# Linear_Regulator.net
KiCad netlist of a schematic drawn in Altium Designer
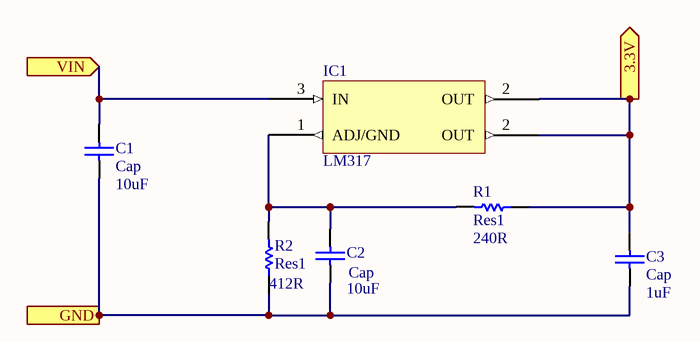
[diagram p0: Linear Regulator.SchDoc]

(export (version "E")
  (design (tool "Eeschema 10.0.6"))
  (components
    (comp (ref "C1")
      (value "Cap")
      (footprint "RAD-0.3")
      (description "Capacitor")
      (fields (field (name "ALTIUM_VALUE") "10uF") (field (name "PUBLISHER") "Altium Limited"))
      (libsource (lib "Miscellaneous Devices") (part "Cap"))
    )
    (comp (ref "C2")
      (value "Cap")
      (footprint "RAD-0.3")
      (description "Capacitor")
      (fields (field (name "ALTIUM_VALUE") "10uF") (field (name "PUBLISHER") "Altium Limited"))
      (libsource (lib "Miscellaneous Devices") (part "Cap"))
    )
    (comp (ref "C3")
      (value "Cap")
      (footprint "RAD-0.3")
      (description "Capacitor")
      (fields (field (name "ALTIUM_VALUE") "1uF") (field (name "PUBLISHER") "Altium Limited"))
      (libsource (lib "Miscellaneous Devices") (part "Cap"))
    )
    (comp (ref "IC1")
      (value "LM317")
      (footprint "SOT-223")
      (libsource (lib "MainboardSchLib") (part "LM317"))
    )
    (comp (ref "R1")
      (value "Res1")
      (footprint "AXIAL-0.3")
      (description "Resistor")
      (fields (field (name "ALTIUM_VALUE") "240R") (field (name "PUBLISHER") "Altium Limited"))
      (libsource (lib "Miscellaneous Devices") (part "Res1"))
    )
    (comp (ref "R2")
      (value "Res1")
      (footprint "AXIAL-0.3")
      (description "Resistor")
      (fields (field (name "ALTIUM_VALUE") "412R") (field (name "PUBLISHER") "Altium Limited"))
      (libsource (lib "Miscellaneous Devices") (part "Res1"))
    )
  )
  (nets
    (net (code "1") (name "/3.3V") (class "Default")
      (node (ref "C3") (pin "2") (pinfunction "2_2") (pintype "passive"))
      (node (ref "IC1") (pin "2") (pinfunction "OUT_2") (pintype "output"))
      (node (ref "R1") (pin "1") (pinfunction "1_1") (pintype "passive"))
    )
    (net (code "2") (name "/GND") (class "Default")
      (node (ref "C1") (pin "1") (pinfunction "1_1") (pintype "passive"))
      (node (ref "C2") (pin "1") (pinfunction "1_1") (pintype "passive"))
      (node (ref "C3") (pin "1") (pinfunction "1_1") (pintype "passive"))
      (node (ref "R2") (pin "1") (pinfunction "1_1") (pintype "passive"))
    )
    (net (code "3") (name "/VIN") (class "Default")
      (node (ref "C1") (pin "2") (pinfunction "2_2") (pintype "passive"))
      (node (ref "IC1") (pin "3") (pinfunction "IN_3") (pintype "input"))
    )
    (net (code "4") (name "Net-(IC1-ADJ{slash}GND)") (class "Default")
      (node (ref "C2") (pin "2") (pinfunction "2_2") (pintype "passive"))
      (node (ref "IC1") (pin "1") (pinfunction "ADJ/GND_1") (pintype "output"))
      (node (ref "R1") (pin "2") (pinfunction "2_2") (pintype "passive"))
      (node (ref "R2") (pin "2") (pinfunction "2_2") (pintype "passive"))
    )
  )
)
